# mapleCUx_large_330-007.net
KiCad netlist of a schematic drawn in EAGLE
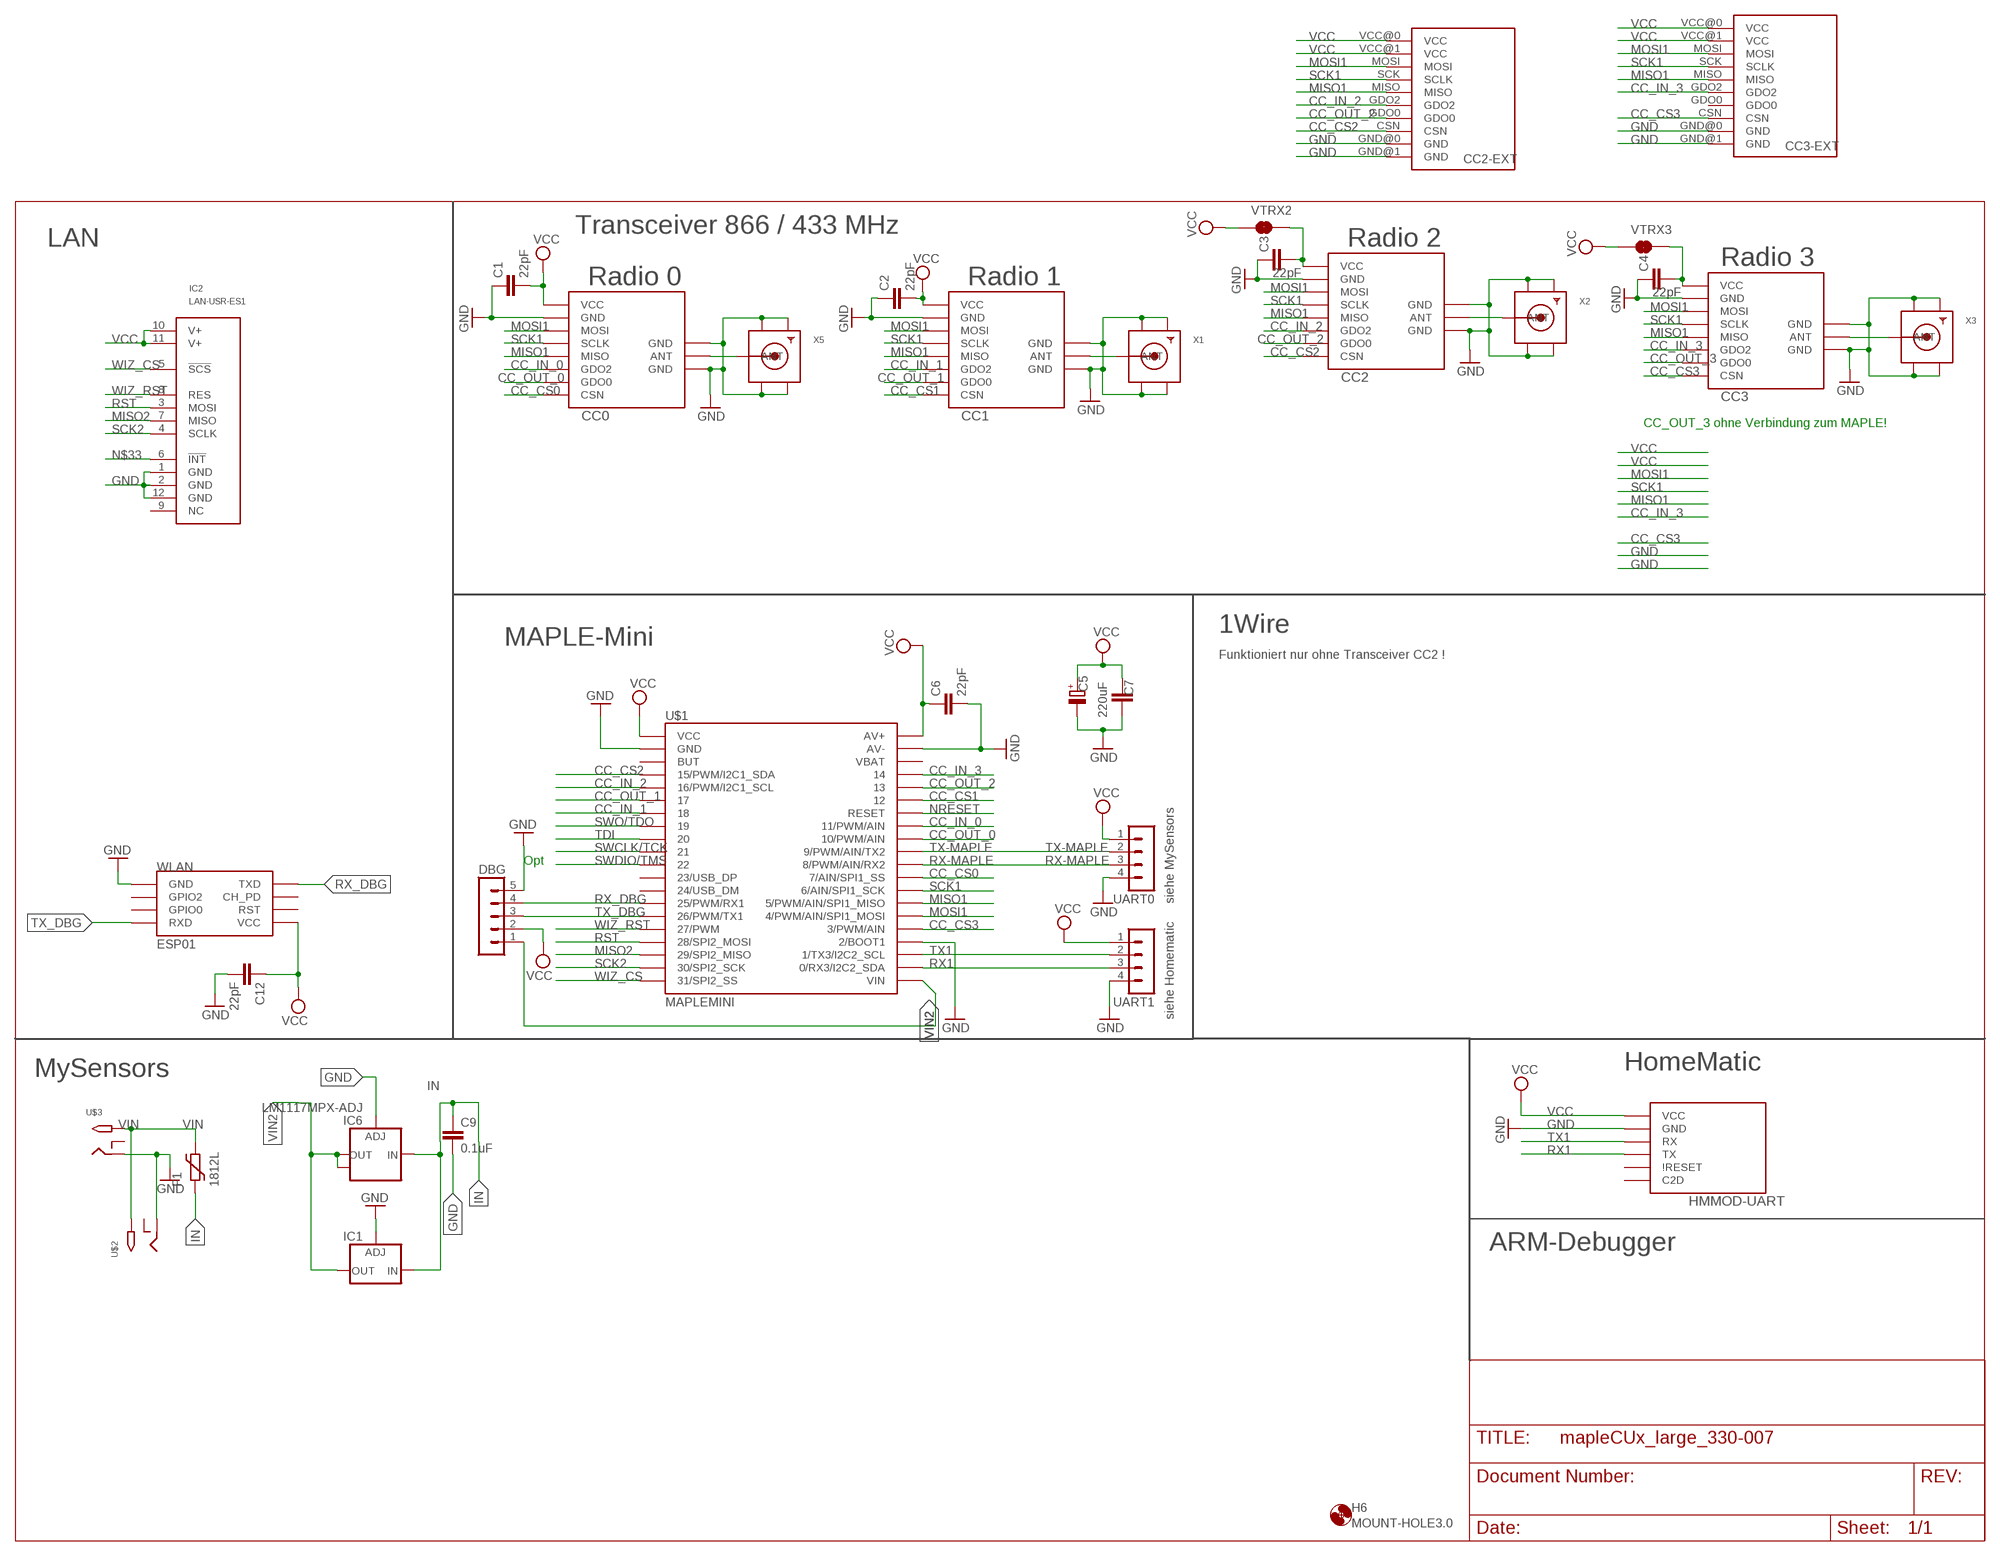
[diagram p0: schematic, sheet 1]

(export (version "E")
  (design (tool "Eeschema 10.0.6"))
  (components
    (comp (ref "C1")
      (value "22pF")
      (footprint "eagle-import:C0805")
      (libsource (lib "eagle-import") (part "C-EUC0805"))
    )
    (comp (ref "C2")
      (value "22pF")
      (footprint "eagle-import:C0805")
      (libsource (lib "eagle-import") (part "C-EUC0805"))
    )
    (comp (ref "C3")
      (value "22pF")
      (footprint "eagle-import:C0805")
      (libsource (lib "eagle-import") (part "C-EUC0805"))
    )
    (comp (ref "C4")
      (value "22pF")
      (footprint "eagle-import:C0805")
      (libsource (lib "eagle-import") (part "C-EUC0805"))
    )
    (comp (ref "C5")
      (value "220uF")
      (footprint "eagle-import:E5-8,5")
      (libsource (lib "eagle-import") (part "CPOL-EUE5-8.5"))
    )
    (comp (ref "C6")
      (value "22pF")
      (footprint "eagle-import:C0805")
      (libsource (lib "eagle-import") (part "C-EUC0805"))
    )
    (comp (ref "C7")
      (value "C-EUC1812")
      (footprint "eagle-import:C1812")
      (libsource (lib "eagle-import") (part "C-EUC1812"))
    )
    (comp (ref "C9")
      (value "0.1uF")
      (footprint "eagle-import:C1206")
      (libsource (lib "eagle-import") (part "C-EUC1206"))
    )
    (comp (ref "C12")
      (value "22pF")
      (footprint "eagle-import:C0805")
      (libsource (lib "eagle-import") (part "C-EUC0805"))
    )
    (comp (ref "CC0")
      (value "CC1101")
      (footprint "eagle-import:CC1101_MODULE1_SMD")
      (libsource (lib "eagle-import") (part "CC1101_MODULE1SMD"))
    )
    (comp (ref "CC1")
      (value "CC1101_MODULE1SMD")
      (footprint "eagle-import:CC1101_MODULE1_SMD")
      (libsource (lib "eagle-import") (part "CC1101_MODULE1SMD"))
    )
    (comp (ref "CC2")
      (value "CC1101_MODULE1SMD")
      (footprint "eagle-import:CC1101_MODULE1_SMD")
      (libsource (lib "eagle-import") (part "CC1101_MODULE1SMD"))
    )
    (comp (ref "CC2-EXT")
      (value "CC1101_MODULE3_DIL")
      (footprint "eagle-import:CC1101_MODULE3_DIL")
      (libsource (lib "eagle-import") (part "CC1101_MODULE3_DIL"))
    )
    (comp (ref "CC3")
      (value "CC1101_MODULE1SMD")
      (footprint "eagle-import:CC1101_MODULE1_SMD")
      (libsource (lib "eagle-import") (part "CC1101_MODULE1SMD"))
    )
    (comp (ref "CC3-EXT")
      (value "CC1101_MODULE3_DIL")
      (footprint "eagle-import:CC1101_MODULE3_DIL")
      (libsource (lib "eagle-import") (part "CC1101_MODULE3_DIL"))
    )
    (comp (ref "DBG")
      (value "MA05-1")
      (footprint "eagle-import:MA05-1")
      (libsource (lib "eagle-import") (part "MA05-1"))
    )
    (comp (ref "F1")
      (value "1812L")
      (footprint "eagle-import:1812L")
      (libsource (lib "eagle-import") (part "1812L"))
    )
    (comp (ref "H6")
      (value "MOUNT-HOLE3.0")
      (footprint "eagle-import:3,0")
      (libsource (lib "eagle-import") (part "MOUNT-HOLE3.0"))
    )
    (comp (ref "HMMOD-UART")
      (value "HM-MOD-UARTDIL")
      (footprint "eagle-import:HM-MOD-UART-DIL")
      (libsource (lib "eagle-import") (part "HM-MOD-UARTDIL"))
    )
    (comp (ref "IC1")
      (value "LD117ADT50TR")
      (footprint "eagle-import:DPACK")
      (libsource (lib "eagle-import") (part "LD117A?DT50TR"))
    )
    (comp (ref "IC2")
      (value "LAN-USR-ES1")
      (footprint "eagle-import:USR-ES1")
      (libsource (lib "eagle-import") (part "LAN-USR-ES1"))
    )
    (comp (ref "IC6")
      (value "LM1117MPX-ADJ")
      (footprint "eagle-import:SOT223")
      (libsource (lib "eagle-import") (part "LM1117MPX-ADJ"))
    )
    (comp (ref "U$1")
      (value "MAPLEMINI")
      (footprint "eagle-import:20-DIP")
      (libsource (lib "eagle-import") (part "MAPLEMINI"))
    )
    (comp (ref "U$2")
      (value "2.1MMJACKTHM")
      (footprint "eagle-import:PJ-102A")
      (libsource (lib "eagle-import") (part "2.1MMJACKTHM"))
    )
    (comp (ref "U$3")
      (value "2.1MMJACKTHM")
      (footprint "eagle-import:PJ-102A")
      (libsource (lib "eagle-import") (part "2.1MMJACKTHM"))
    )
    (comp (ref "UART0")
      (value "MA04-1")
      (footprint "eagle-import:MA04-1")
      (libsource (lib "eagle-import") (part "MA04-1"))
    )
    (comp (ref "UART1")
      (value "MA04-1")
      (footprint "eagle-import:MA04-1")
      (libsource (lib "eagle-import") (part "MA04-1"))
    )
    (comp (ref "VTRX2")
      (value "JUMPER-SMT_2_NC_TRACE_SILK")
      (footprint "eagle-import:SMT-JUMPER_2_NC_TRACE_SILK")
      (libsource (lib "eagle-import") (part "JUMPER-SMT_2_NC_TRACE_SILK"))
    )
    (comp (ref "VTRX3")
      (value "JUMPER-SMT_2_NC_TRACE_SILK")
      (footprint "eagle-import:SMT-JUMPER_2_NC_TRACE_SILK")
      (libsource (lib "eagle-import") (part "JUMPER-SMT_2_NC_TRACE_SILK"))
    )
    (comp (ref "WLAN")
      (value "ESP01")
      (footprint "eagle-import:ESP01")
      (libsource (lib "eagle-import") (part "ESP01"))
    )
    (comp (ref "X1")
      (value "SMACONNECTOR_EDGE")
      (footprint "eagle-import:SMA_EDGELAUNCH")
      (libsource (lib "eagle-import") (part "SMACONNECTOR_EDGE"))
    )
    (comp (ref "X2")
      (value "SMACONNECTOR_EDGE")
      (footprint "eagle-import:SMA_EDGELAUNCH")
      (libsource (lib "eagle-import") (part "SMACONNECTOR_EDGE"))
    )
    (comp (ref "X3")
      (value "SMACONNECTOR_EDGE")
      (footprint "eagle-import:SMA_EDGELAUNCH")
      (libsource (lib "eagle-import") (part "SMACONNECTOR_EDGE"))
    )
    (comp (ref "X5")
      (value "SMACONNECTOR_EDGE")
      (footprint "eagle-import:SMA_EDGELAUNCH")
      (libsource (lib "eagle-import") (part "SMACONNECTOR_EDGE"))
    )
  )
  (nets
    (net (code "1") (name "/CC_CS0") (class "Default")
      (node (ref "CC0") (pin "CSN") (pinfunction "CSN_CSN") (pintype "bidirectional"))
      (node (ref "U$1") (pin "29") (pinfunction "7/AIN/SPI1_SS_29") (pintype "bidirectional"))
    )
    (net (code "2") (name "/CC_CS1") (class "Default")
      (node (ref "CC1") (pin "CSN") (pinfunction "CSN_CSN") (pintype "bidirectional"))
      (node (ref "U$1") (pin "35") (pinfunction "12_35") (pintype "bidirectional"))
    )
    (net (code "3") (name "/CC_CS2") (class "Default")
      (node (ref "CC2") (pin "CSN") (pinfunction "CSN_CSN") (pintype "bidirectional"))
      (node (ref "CC2-EXT") (pin "CSN") (pinfunction "CSN_CSN") (pintype "bidirectional"))
      (node (ref "U$1") (pin "4") (pinfunction "15/PWM/I2C1_SDA_4") (pintype "bidirectional"))
    )
    (net (code "4") (name "/CC_CS3") (class "Default")
      (node (ref "CC3") (pin "CSN") (pinfunction "CSN_CSN") (pintype "bidirectional"))
      (node (ref "CC3-EXT") (pin "CSN") (pinfunction "CSN_CSN") (pintype "bidirectional"))
      (node (ref "U$1") (pin "25") (pinfunction "3/PWM/AIN_25") (pintype "bidirectional"))
    )
    (net (code "5") (name "/CC_IN_0") (class "Default")
      (node (ref "CC0") (pin "GDO2") (pinfunction "GDO2_GDO2") (pintype "bidirectional"))
      (node (ref "U$1") (pin "33") (pinfunction "11/PWM/AIN_33") (pintype "bidirectional"))
    )
    (net (code "6") (name "/CC_IN_1") (class "Default")
      (node (ref "CC1") (pin "GDO2") (pinfunction "GDO2_GDO2") (pintype "bidirectional"))
      (node (ref "U$1") (pin "7") (pinfunction "18_7") (pintype "bidirectional"))
    )
    (net (code "7") (name "/CC_IN_2") (class "Default")
      (node (ref "CC2") (pin "GDO2") (pinfunction "GDO2_GDO2") (pintype "bidirectional"))
      (node (ref "CC2-EXT") (pin "GDO2") (pinfunction "GDO2_GDO2") (pintype "bidirectional"))
      (node (ref "U$1") (pin "5") (pinfunction "16/PWM/I2C1_SCL_5") (pintype "bidirectional"))
    )
    (net (code "8") (name "/CC_IN_3") (class "Default")
      (node (ref "CC3") (pin "GDO2") (pinfunction "GDO2_GDO2") (pintype "bidirectional"))
      (node (ref "CC3-EXT") (pin "GDO2") (pinfunction "GDO2_GDO2") (pintype "bidirectional"))
      (node (ref "U$1") (pin "37") (pinfunction "14_37") (pintype "bidirectional"))
    )
    (net (code "9") (name "/CC_OUT_0") (class "Default")
      (node (ref "CC0") (pin "GDO0") (pinfunction "GDO0_GDO0") (pintype "bidirectional"))
      (node (ref "U$1") (pin "32") (pinfunction "10/PWM/AIN_32") (pintype "bidirectional"))
    )
    (net (code "10") (name "/CC_OUT_1") (class "Default")
      (node (ref "CC1") (pin "GDO0") (pinfunction "GDO0_GDO0") (pintype "bidirectional"))
      (node (ref "U$1") (pin "6") (pinfunction "17_6") (pintype "bidirectional"))
    )
    (net (code "11") (name "/CC_OUT_2") (class "Default")
      (node (ref "CC2") (pin "GDO0") (pinfunction "GDO0_GDO0") (pintype "bidirectional"))
      (node (ref "CC2-EXT") (pin "GDO0") (pinfunction "GDO0_GDO0") (pintype "bidirectional"))
      (node (ref "U$1") (pin "36") (pinfunction "13_36") (pintype "bidirectional"))
    )
    (net (code "12") (name "/CC_OUT_3") (class "Default")
      (node (ref "CC3") (pin "GDO0") (pinfunction "GDO0_GDO0") (pintype "bidirectional"))
    )
    (net (code "13") (name "/MISO1") (class "Default")
      (node (ref "CC0") (pin "MISO") (pinfunction "MISO_MISO") (pintype "bidirectional"))
      (node (ref "CC1") (pin "MISO") (pinfunction "MISO_MISO") (pintype "bidirectional"))
      (node (ref "CC2") (pin "MISO") (pinfunction "MISO_MISO") (pintype "bidirectional"))
      (node (ref "CC2-EXT") (pin "MISO") (pinfunction "MISO_MISO") (pintype "bidirectional"))
      (node (ref "CC3") (pin "MISO") (pinfunction "MISO_MISO") (pintype "bidirectional"))
      (node (ref "CC3-EXT") (pin "MISO") (pinfunction "MISO_MISO") (pintype "bidirectional"))
      (node (ref "U$1") (pin "27") (pinfunction "5/PWM/AIN/SPI1_MISO_27") (pintype "bidirectional"))
    )
    (net (code "14") (name "/MISO2") (class "Default")
      (node (ref "IC2") (pin "7") (pinfunction "MISO_7") (pintype "bidirectional"))
      (node (ref "U$1") (pin "18") (pinfunction "29/SPI2_MISO_18") (pintype "bidirectional"))
    )
    (net (code "15") (name "/MOSI1") (class "Default")
      (node (ref "CC0") (pin "MOSI") (pinfunction "MOSI_MOSI") (pintype "bidirectional"))
      (node (ref "CC1") (pin "MOSI") (pinfunction "MOSI_MOSI") (pintype "bidirectional"))
      (node (ref "CC2") (pin "MOSI") (pinfunction "MOSI_MOSI") (pintype "bidirectional"))
      (node (ref "CC2-EXT") (pin "MOSI") (pinfunction "MOSI_MOSI") (pintype "bidirectional"))
      (node (ref "CC3") (pin "MOSI") (pinfunction "MOSI_MOSI") (pintype "bidirectional"))
      (node (ref "CC3-EXT") (pin "MOSI") (pinfunction "MOSI_MOSI") (pintype "bidirectional"))
      (node (ref "U$1") (pin "26") (pinfunction "4/PWM/AIN/SPI1_MOSI_26") (pintype "bidirectional"))
    )
    (net (code "16") (name "/N$33") (class "Default")
      (node (ref "IC2") (pin "6") (pinfunction "~{INT}_6") (pintype "output"))
    )
    (net (code "17") (name "/NRESET") (class "Default")
      (node (ref "U$1") (pin "34") (pinfunction "RESET_34") (pintype "bidirectional"))
    )
    (net (code "18") (name "/RST") (class "Default")
      (node (ref "IC2") (pin "3") (pinfunction "MOSI_3") (pintype "bidirectional"))
      (node (ref "U$1") (pin "17") (pinfunction "28/SPI2_MOSI_17") (pintype "bidirectional"))
    )
    (net (code "19") (name "/RX-MAPLE") (class "Default")
      (node (ref "U$1") (pin "30") (pinfunction "8/PWM/AIN/RX2_30") (pintype "bidirectional"))
      (node (ref "UART0") (pin "3") (pinfunction "3_3") (pintype "passive"))
    )
    (net (code "20") (name "/RX1") (class "Default")
      (node (ref "HMMOD-UART") (pin "5") (pinfunction "TX_5") (pintype "bidirectional"))
      (node (ref "U$1") (pin "22") (pinfunction "0/RX3/I2C2_SDA_22") (pintype "bidirectional"))
      (node (ref "UART1") (pin "3") (pinfunction "3_3") (pintype "passive"))
    )
    (net (code "21") (name "/SCK1") (class "Default")
      (node (ref "CC0") (pin "SCLK") (pinfunction "SCLK_SCLK") (pintype "bidirectional"))
      (node (ref "CC1") (pin "SCLK") (pinfunction "SCLK_SCLK") (pintype "bidirectional"))
      (node (ref "CC2") (pin "SCLK") (pinfunction "SCLK_SCLK") (pintype "bidirectional"))
      (node (ref "CC2-EXT") (pin "SCK") (pinfunction "SCLK_SCK") (pintype "bidirectional"))
      (node (ref "CC3") (pin "SCLK") (pinfunction "SCLK_SCLK") (pintype "bidirectional"))
      (node (ref "CC3-EXT") (pin "SCK") (pinfunction "SCLK_SCK") (pintype "bidirectional"))
      (node (ref "U$1") (pin "28") (pinfunction "6/AIN/SPI1_SCK_28") (pintype "bidirectional"))
    )
    (net (code "22") (name "/SCK2") (class "Default")
      (node (ref "IC2") (pin "4") (pinfunction "SCLK_4") (pintype "input"))
      (node (ref "U$1") (pin "19") (pinfunction "30/SPI2_SCK_19") (pintype "bidirectional"))
    )
    (net (code "23") (name "/SWCLK{slash}TCK") (class "Default")
      (node (ref "U$1") (pin "10") (pinfunction "21_10") (pintype "bidirectional"))
    )
    (net (code "24") (name "/SWDIO{slash}TMS") (class "Default")
      (node (ref "U$1") (pin "11") (pinfunction "22_11") (pintype "bidirectional"))
    )
    (net (code "25") (name "/SWO{slash}TDO") (class "Default")
      (node (ref "U$1") (pin "8") (pinfunction "19_8") (pintype "bidirectional"))
    )
    (net (code "26") (name "/TDI") (class "Default")
      (node (ref "U$1") (pin "9") (pinfunction "20_9") (pintype "bidirectional"))
    )
    (net (code "27") (name "/TX-MAPLE") (class "Default")
      (node (ref "U$1") (pin "31") (pinfunction "9/PWM/AIN/TX2_31") (pintype "bidirectional"))
      (node (ref "UART0") (pin "2") (pinfunction "2_2") (pintype "passive"))
    )
    (net (code "28") (name "/TX1") (class "Default")
      (node (ref "HMMOD-UART") (pin "6") (pinfunction "RX_6") (pintype "bidirectional"))
      (node (ref "U$1") (pin "23") (pinfunction "1/TX3/I2C2_SCL_23") (pintype "bidirectional"))
      (node (ref "UART1") (pin "2") (pinfunction "2_2") (pintype "passive"))
    )
    (net (code "29") (name "/VIN") (class "Default")
      (node (ref "F1") (pin "P$2") (pinfunction "2_P$2") (pintype "passive"))
      (node (ref "U$2") (pin "TIP") (pinfunction "TIP_TIP") (pintype "bidirectional"))
      (node (ref "U$3") (pin "TIP") (pinfunction "TIP_TIP") (pintype "bidirectional"))
    )
    (net (code "30") (name "/WIZ_CS") (class "Default")
      (node (ref "IC2") (pin "5") (pinfunction "~{SCS}_5") (pintype "input"))
      (node (ref "U$1") (pin "20") (pinfunction "31/SPI2_SS_20") (pintype "bidirectional"))
    )
    (net (code "31") (name "/WIZ_RST") (class "Default")
      (node (ref "IC2") (pin "8") (pinfunction "RES_8") (pintype "input"))
      (node (ref "U$1") (pin "16") (pinfunction "27/PWM_16") (pintype "bidirectional"))
    )
    (net (code "32") (name "GND") (class "Default")
      (node (ref "C1") (pin "1") (pinfunction "1_1") (pintype "passive"))
      (node (ref "C12") (pin "2") (pinfunction "2_2") (pintype "passive"))
      (node (ref "C2") (pin "1") (pinfunction "1_1") (pintype "passive"))
      (node (ref "C3") (pin "1") (pinfunction "1_1") (pintype "passive"))
      (node (ref "C4") (pin "1") (pinfunction "1_1") (pintype "passive"))
      (node (ref "C5") (pin "-") (pinfunction "-_-") (pintype "passive"))
      (node (ref "C6") (pin "2") (pinfunction "2_2") (pintype "passive"))
      (node (ref "C7") (pin "1") (pinfunction "1_1") (pintype "passive"))
      (node (ref "C9") (pin "2") (pinfunction "2_2") (pintype "passive"))
      (node (ref "CC0") (pin "GND@0") (pinfunction "GND_GND@0") (pintype "power_in"))
      (node (ref "CC0") (pin "GND@1") (pinfunction "GND_GND@1") (pintype "power_in"))
      (node (ref "CC0") (pin "GND@2") (pinfunction "GND_GND@2") (pintype "power_in"))
      (node (ref "CC1") (pin "GND@0") (pinfunction "GND_GND@0") (pintype "power_in"))
      (node (ref "CC1") (pin "GND@1") (pinfunction "GND_GND@1") (pintype "power_in"))
      (node (ref "CC1") (pin "GND@2") (pinfunction "GND_GND@2") (pintype "power_in"))
      (node (ref "CC2") (pin "GND@0") (pinfunction "GND_GND@0") (pintype "power_in"))
      (node (ref "CC2") (pin "GND@1") (pinfunction "GND_GND@1") (pintype "power_in"))
      (node (ref "CC2") (pin "GND@2") (pinfunction "GND_GND@2") (pintype "power_in"))
      (node (ref "CC2-EXT") (pin "GND@0") (pinfunction "GND_GND@0") (pintype "power_in"))
      (node (ref "CC2-EXT") (pin "GND@1") (pinfunction "GND_GND@1") (pintype "power_in"))
      (node (ref "CC3") (pin "GND@0") (pinfunction "GND_GND@0") (pintype "power_in"))
      (node (ref "CC3") (pin "GND@1") (pinfunction "GND_GND@1") (pintype "power_in"))
      (node (ref "CC3") (pin "GND@2") (pinfunction "GND_GND@2") (pintype "power_in"))
      (node (ref "CC3-EXT") (pin "GND@0") (pinfunction "GND_GND@0") (pintype "power_in"))
      (node (ref "CC3-EXT") (pin "GND@1") (pinfunction "GND_GND@1") (pintype "power_in"))
      (node (ref "DBG") (pin "5") (pinfunction "5_5") (pintype "passive"))
      (node (ref "HMMOD-UART") (pin "2") (pinfunction "GND_2") (pintype "power_in"))
      (node (ref "IC1") (pin "1") (pinfunction "ADJ_1") (pintype "input"))
      (node (ref "IC2") (pin "1") (pinfunction "GND_1") (pintype "power_in"))
      (node (ref "IC2") (pin "12") (pinfunction "GND_12") (pintype "power_in"))
      (node (ref "IC2") (pin "2") (pinfunction "GND_2") (pintype "power_in"))
      (node (ref "IC6") (pin "1") (pinfunction "ADJ_1") (pintype "input"))
      (node (ref "U$1") (pin "2") (pinfunction "GND_2") (pintype "bidirectional"))
      (node (ref "U$1") (pin "24") (pinfunction "2/BOOT1_24") (pintype "bidirectional"))
      (node (ref "U$1") (pin "39") (pinfunction "AV-_39") (pintype "bidirectional"))
      (node (ref "U$2") (pin "RING") (pinfunction "RING_RING") (pintype "bidirectional"))
      (node (ref "U$3") (pin "RING") (pinfunction "RING_RING") (pintype "bidirectional"))
      (node (ref "UART0") (pin "4") (pinfunction "4_4") (pintype "passive"))
      (node (ref "UART1") (pin "4") (pinfunction "4_4") (pintype "passive"))
      (node (ref "WLAN") (pin "GND") (pinfunction "GND_GND") (pintype "bidirectional"))
      (node (ref "X1") (pin "GND@1") (pinfunction "GND4_GND@1") (pintype "power_in"))
      (node (ref "X1") (pin "GND@2") (pinfunction "GND3_GND@2") (pintype "power_in"))
      (node (ref "X1") (pin "GND@3") (pinfunction "GND2_GND@3") (pintype "power_in"))
      (node (ref "X1") (pin "GND@4") (pinfunction "GND1_GND@4") (pintype "power_in"))
      (node (ref "X2") (pin "GND@1") (pinfunction "GND4_GND@1") (pintype "power_in"))
      (node (ref "X2") (pin "GND@2") (pinfunction "GND3_GND@2") (pintype "power_in"))
      (node (ref "X2") (pin "GND@3") (pinfunction "GND2_GND@3") (pintype "power_in"))
      (node (ref "X2") (pin "GND@4") (pinfunction "GND1_GND@4") (pintype "power_in"))
      (node (ref "X3") (pin "GND@1") (pinfunction "GND4_GND@1") (pintype "power_in"))
      (node (ref "X3") (pin "GND@2") (pinfunction "GND3_GND@2") (pintype "power_in"))
      (node (ref "X3") (pin "GND@3") (pinfunction "GND2_GND@3") (pintype "power_in"))
      (node (ref "X3") (pin "GND@4") (pinfunction "GND1_GND@4") (pintype "power_in"))
      (node (ref "X5") (pin "GND@1") (pinfunction "GND4_GND@1") (pintype "power_in"))
      (node (ref "X5") (pin "GND@2") (pinfunction "GND3_GND@2") (pintype "power_in"))
      (node (ref "X5") (pin "GND@3") (pinfunction "GND2_GND@3") (pintype "power_in"))
      (node (ref "X5") (pin "GND@4") (pinfunction "GND1_GND@4") (pintype "power_in"))
    )
    (net (code "33") (name "IN") (class "Default")
      (node (ref "C9") (pin "1") (pinfunction "1_1") (pintype "passive"))
      (node (ref "F1") (pin "P$1") (pinfunction "1_P$1") (pintype "passive"))
      (node (ref "IC1") (pin "3") (pinfunction "IN_3") (pintype "input"))
      (node (ref "IC6") (pin "3") (pinfunction "IN_3") (pintype "input"))
    )
    (net (code "34") (name "Net-(C3-Pad2)") (class "Default")
      (node (ref "C3") (pin "2") (pinfunction "2_2") (pintype "passive"))
      (node (ref "CC2") (pin "VCC") (pinfunction "VCC_VCC") (pintype "power_in"))
      (node (ref "VTRX2") (pin "2") (pinfunction "2_2") (pintype "passive"))
    )
    (net (code "35") (name "Net-(C4-Pad2)") (class "Default")
      (node (ref "C4") (pin "2") (pinfunction "2_2") (pintype "passive"))
      (node (ref "CC3") (pin "VCC") (pinfunction "VCC_VCC") (pintype "power_in"))
      (node (ref "VTRX3") (pin "2") (pinfunction "2_2") (pintype "passive"))
    )
    (net (code "36") (name "Net-(X1-ANT)") (class "Default")
      (node (ref "CC1") (pin "ANT") (pinfunction "ANT_ANT") (pintype "output"))
      (node (ref "X1") (pin "P") (pinfunction "ANT_P") (pintype "bidirectional"))
    )
    (net (code "37") (name "Net-(X2-ANT)") (class "Default")
      (node (ref "CC2") (pin "ANT") (pinfunction "ANT_ANT") (pintype "output"))
      (node (ref "X2") (pin "P") (pinfunction "ANT_P") (pintype "bidirectional"))
    )
    (net (code "38") (name "Net-(X3-ANT)") (class "Default")
      (node (ref "CC3") (pin "ANT") (pinfunction "ANT_ANT") (pintype "output"))
      (node (ref "X3") (pin "P") (pinfunction "ANT_P") (pintype "bidirectional"))
    )
    (net (code "39") (name "Net-(X5-ANT)") (class "Default")
      (node (ref "CC0") (pin "ANT") (pinfunction "ANT_ANT") (pintype "output"))
      (node (ref "X5") (pin "P") (pinfunction "ANT_P") (pintype "bidirectional"))
    )
    (net (code "40") (name "RX_DBG") (class "Default")
      (node (ref "DBG") (pin "4") (pinfunction "4_4") (pintype "passive"))
      (node (ref "U$1") (pin "14") (pinfunction "25/PWM/RX1_14") (pintype "bidirectional"))
      (node (ref "WLAN") (pin "TX") (pinfunction "TXD_TX") (pintype "bidirectional"))
    )
    (net (code "41") (name "TX_DBG") (class "Default")
      (node (ref "DBG") (pin "3") (pinfunction "3_3") (pintype "passive"))
      (node (ref "U$1") (pin "15") (pinfunction "26/PWM/TX1_15") (pintype "bidirectional"))
      (node (ref "WLAN") (pin "RX") (pinfunction "RXD_RX") (pintype "bidirectional"))
    )
    (net (code "42") (name "VCC") (class "Default")
      (node (ref "C1") (pin "2") (pinfunction "2_2") (pintype "passive"))
      (node (ref "C12") (pin "1") (pinfunction "1_1") (pintype "passive"))
      (node (ref "C2") (pin "2") (pinfunction "2_2") (pintype "passive"))
      (node (ref "C5") (pin "+") (pinfunction "+_+") (pintype "passive"))
      (node (ref "C6") (pin "1") (pinfunction "1_1") (pintype "passive"))
      (node (ref "C7") (pin "2") (pinfunction "2_2") (pintype "passive"))
      (node (ref "CC0") (pin "VCC") (pinfunction "VCC_VCC") (pintype "power_in"))
      (node (ref "CC1") (pin "VCC") (pinfunction "VCC_VCC") (pintype "power_in"))
      (node (ref "CC2-EXT") (pin "VCC@0") (pinfunction "VCC_VCC@0") (pintype "power_in"))
      (node (ref "CC2-EXT") (pin "VCC@1") (pinfunction "VCC_VCC@1") (pintype "power_in"))
      (node (ref "CC3-EXT") (pin "VCC@0") (pinfunction "VCC_VCC@0") (pintype "power_in"))
      (node (ref "CC3-EXT") (pin "VCC@1") (pinfunction "VCC_VCC@1") (pintype "power_in"))
      (node (ref "DBG") (pin "2") (pinfunction "2_2") (pintype "passive"))
      (node (ref "HMMOD-UART") (pin "1") (pinfunction "VCC_1") (pintype "power_in"))
      (node (ref "IC2") (pin "10") (pinfunction "V+_10") (pintype "power_in"))
      (node (ref "IC2") (pin "11") (pinfunction "V+_11") (pintype "power_in"))
      (node (ref "U$1") (pin "1") (pinfunction "VCC_1") (pintype "bidirectional"))
      (node (ref "U$1") (pin "40") (pinfunction "AV+_40") (pintype "bidirectional"))
      (node (ref "UART0") (pin "1") (pinfunction "1_1") (pintype "passive"))
      (node (ref "UART1") (pin "1") (pinfunction "1_1") (pintype "passive"))
      (node (ref "VTRX2") (pin "1") (pinfunction "1_1") (pintype "passive"))
      (node (ref "VTRX3") (pin "1") (pinfunction "1_1") (pintype "passive"))
      (node (ref "WLAN") (pin "VCC") (pinfunction "VCC_VCC") (pintype "bidirectional"))
    )
    (net (code "43") (name "VIN2") (class "Default")
      (node (ref "DBG") (pin "1") (pinfunction "1_1") (pintype "passive"))
      (node (ref "IC1") (pin "4") (pinfunction "OUT_4") (pintype "passive"))
      (node (ref "IC6") (pin "2") (pinfunction "OUT_2") (pintype "passive"))
      (node (ref "IC6") (pin "TAB") (pinfunction "OUT1_TAB") (pintype "passive"))
      (node (ref "U$1") (pin "21") (pinfunction "VIN_21") (pintype "bidirectional"))
    )
    (net (code "44") (name "unconnected-(CC3-EXT-PadGDO0)") (class "Default")
      (node (ref "CC3-EXT") (pin "GDO0") (pinfunction "GDO0_GDO0") (pintype "bidirectional"))
    )
    (net (code "45") (name "unconnected-(HMMOD-UART-C2D-Pad3)") (class "Default")
      (node (ref "HMMOD-UART") (pin "3") (pinfunction "C2D_3") (pintype "bidirectional"))
    )
    (net (code "46") (name "unconnected-(HMMOD-UART-\\~{RESET}-Pad4)") (class "Default")
      (node (ref "HMMOD-UART") (pin "4") (pinfunction "\\~{RESET}_4") (pintype "bidirectional"))
    )
    (net (code "47") (name "unconnected-(IC2-NC-Pad9)") (class "Default")
      (node (ref "IC2") (pin "9") (pinfunction "NC_9") (pintype "no_connect"))
    )
    (net (code "48") (name "unconnected-(U$1-23{slash}USB_DP-Pad12)") (class "Default")
      (node (ref "U$1") (pin "12") (pinfunction "23/USB_DP_12") (pintype "bidirectional"))
    )
    (net (code "49") (name "unconnected-(U$1-24{slash}USB_DM-Pad13)") (class "Default")
      (node (ref "U$1") (pin "13") (pinfunction "24/USB_DM_13") (pintype "bidirectional"))
    )
    (net (code "50") (name "unconnected-(U$1-BUT-Pad3)") (class "Default")
      (node (ref "U$1") (pin "3") (pinfunction "BUT_3") (pintype "bidirectional"))
    )
    (net (code "51") (name "unconnected-(U$1-VBAT-Pad38)") (class "Default")
      (node (ref "U$1") (pin "38") (pinfunction "VBAT_38") (pintype "bidirectional"))
    )
    (net (code "52") (name "unconnected-(U$2-PadRING_SW)") (class "Default")
      (node (ref "U$2") (pin "RING_SW") (pinfunction "RING_SW_RING_SW") (pintype "bidirectional"))
    )
    (net (code "53") (name "unconnected-(U$3-PadRING_SW)") (class "Default")
      (node (ref "U$3") (pin "RING_SW") (pinfunction "RING_SW_RING_SW") (pintype "bidirectional"))
    )
    (net (code "54") (name "unconnected-(WLAN-PadCH_PD)") (class "Default")
      (node (ref "WLAN") (pin "CH_PD") (pinfunction "CH_PD_CH_PD") (pintype "bidirectional"))
    )
    (net (code "55") (name "unconnected-(WLAN-PadGPIO0)") (class "Default")
      (node (ref "WLAN") (pin "GPIO0") (pinfunction "GPIO0_GPIO0") (pintype "bidirectional"))
    )
    (net (code "56") (name "unconnected-(WLAN-PadGPIO2)") (class "Default")
      (node (ref "WLAN") (pin "GPIO2") (pinfunction "GPIO2_GPIO2") (pintype "bidirectional"))
    )
    (net (code "57") (name "unconnected-(WLAN-PadRST)") (class "Default")
      (node (ref "WLAN") (pin "RST") (pinfunction "RST_RST") (pintype "bidirectional"))
    )
  )
)
